# ONOFRE_SWITCH_SHIELD_3_0.net
KiCad netlist of a schematic drawn in EAGLE
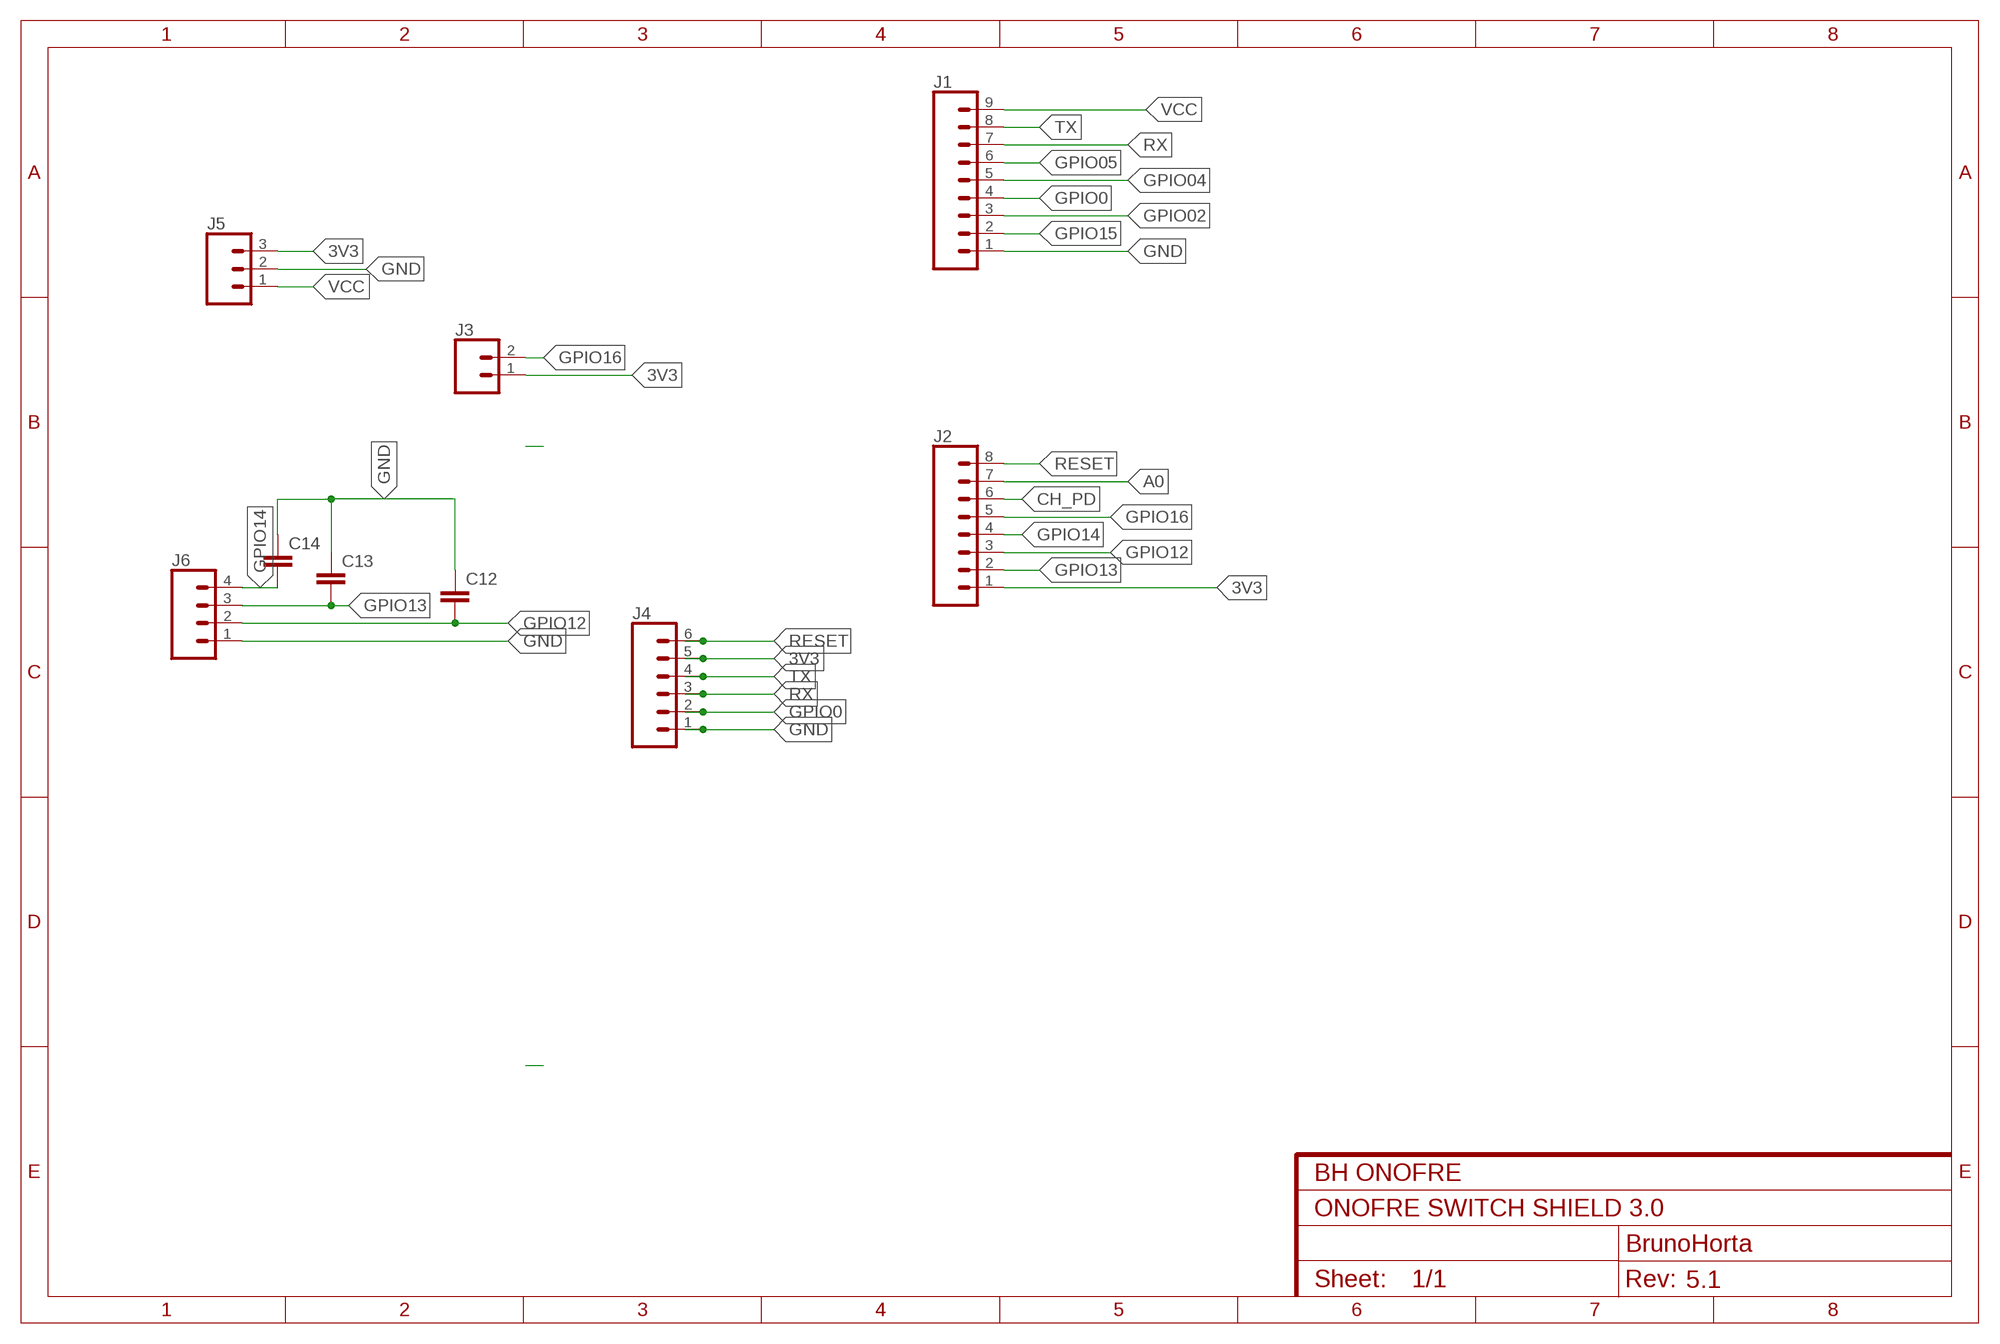
[diagram p0: schematic, sheet 1]

(export (version "E")
  (design (tool "Eeschema 10.0.6"))
  (components
    (comp (ref "C12")
      (value "C-EUC0805")
      (footprint "eagle-import:C0805")
      (libsource (lib "eagle-import") (part "C-EUC0805"))
    )
    (comp (ref "C13")
      (value "C-EUC0805")
      (footprint "eagle-import:C0805")
      (libsource (lib "eagle-import") (part "C-EUC0805"))
    )
    (comp (ref "C14")
      (value "C-EUC0805")
      (footprint "eagle-import:C0805")
      (libsource (lib "eagle-import") (part "C-EUC0805"))
    )
    (comp (ref "J1")
      (value "CONN_09")
      (footprint "eagle-import:1X09")
      (libsource (lib "eagle-import") (part "CONN_09"))
    )
    (comp (ref "J2")
      (value "CONN_08\"")
      (footprint "eagle-import:1X08")
      (libsource (lib "eagle-import") (part "CONN_08{dblquote}"))
    )
    (comp (ref "J3")
      (value "CONN_02")
      (footprint "eagle-import:1X02")
      (libsource (lib "eagle-import") (part "CONN_02"))
    )
    (comp (ref "J4")
      (value "CONN_06NO_SILK_NO_POP")
      (footprint "eagle-import:1X06_NO_SILK")
      (libsource (lib "eagle-import") (part "CONN_06NO_SILK_NO_POP"))
    )
    (comp (ref "J5")
      (value "CONN_03")
      (footprint "eagle-import:1X03")
      (libsource (lib "eagle-import") (part "CONN_03"))
    )
    (comp (ref "J6")
      (value "CONN_04")
      (footprint "eagle-import:1X04")
      (libsource (lib "eagle-import") (part "CONN_04"))
    )
  )
  (nets
    (net (code "1") (name "3V3") (class "Default")
      (node (ref "J2") (pin "1") (pinfunction "1_1") (pintype "passive"))
      (node (ref "J3") (pin "1") (pinfunction "1_1") (pintype "passive"))
      (node (ref "J4") (pin "5") (pinfunction "5_5") (pintype "passive"))
      (node (ref "J5") (pin "3") (pinfunction "3_3") (pintype "passive"))
    )
    (net (code "2") (name "A0") (class "Default")
      (node (ref "J2") (pin "7") (pinfunction "7_7") (pintype "passive"))
    )
    (net (code "3") (name "CH_PD") (class "Default")
      (node (ref "J2") (pin "6") (pinfunction "6_6") (pintype "passive"))
    )
    (net (code "4") (name "GND") (class "Default")
      (node (ref "C12") (pin "1") (pinfunction "1_1") (pintype "passive"))
      (node (ref "C13") (pin "1") (pinfunction "1_1") (pintype "passive"))
      (node (ref "C14") (pin "1") (pinfunction "1_1") (pintype "passive"))
      (node (ref "J1") (pin "1") (pinfunction "1_1") (pintype "passive"))
      (node (ref "J4") (pin "1") (pinfunction "1_1") (pintype "passive"))
      (node (ref "J5") (pin "2") (pinfunction "2_2") (pintype "passive"))
      (node (ref "J6") (pin "1") (pinfunction "1_1") (pintype "passive"))
    )
    (net (code "5") (name "GPIO0") (class "Default")
      (node (ref "J1") (pin "4") (pinfunction "4_4") (pintype "passive"))
      (node (ref "J4") (pin "2") (pinfunction "2_2") (pintype "passive"))
    )
    (net (code "6") (name "GPIO02") (class "Default")
      (node (ref "J1") (pin "3") (pinfunction "3_3") (pintype "passive"))
    )
    (net (code "7") (name "GPIO04") (class "Default")
      (node (ref "J1") (pin "5") (pinfunction "5_5") (pintype "passive"))
    )
    (net (code "8") (name "GPIO05") (class "Default")
      (node (ref "J1") (pin "6") (pinfunction "6_6") (pintype "passive"))
    )
    (net (code "9") (name "GPIO12") (class "Default")
      (node (ref "C12") (pin "2") (pinfunction "2_2") (pintype "passive"))
      (node (ref "J2") (pin "3") (pinfunction "3_3") (pintype "passive"))
      (node (ref "J6") (pin "2") (pinfunction "2_2") (pintype "passive"))
    )
    (net (code "10") (name "GPIO13") (class "Default")
      (node (ref "C13") (pin "2") (pinfunction "2_2") (pintype "passive"))
      (node (ref "J2") (pin "2") (pinfunction "2_2") (pintype "passive"))
      (node (ref "J6") (pin "3") (pinfunction "3_3") (pintype "passive"))
    )
    (net (code "11") (name "GPIO14") (class "Default")
      (node (ref "C14") (pin "2") (pinfunction "2_2") (pintype "passive"))
      (node (ref "J2") (pin "4") (pinfunction "4_4") (pintype "passive"))
      (node (ref "J6") (pin "4") (pinfunction "4_4") (pintype "passive"))
    )
    (net (code "12") (name "GPIO15") (class "Default")
      (node (ref "J1") (pin "2") (pinfunction "2_2") (pintype "passive"))
    )
    (net (code "13") (name "GPIO16") (class "Default")
      (node (ref "J2") (pin "5") (pinfunction "5_5") (pintype "passive"))
      (node (ref "J3") (pin "2") (pinfunction "2_2") (pintype "passive"))
    )
    (net (code "14") (name "RESET") (class "Default")
      (node (ref "J2") (pin "8") (pinfunction "8_8") (pintype "passive"))
      (node (ref "J4") (pin "6") (pinfunction "6_6") (pintype "passive"))
    )
    (net (code "15") (name "RX") (class "Default")
      (node (ref "J1") (pin "7") (pinfunction "7_7") (pintype "passive"))
      (node (ref "J4") (pin "3") (pinfunction "3_3") (pintype "passive"))
    )
    (net (code "16") (name "TX") (class "Default")
      (node (ref "J1") (pin "8") (pinfunction "8_8") (pintype "passive"))
      (node (ref "J4") (pin "4") (pinfunction "4_4") (pintype "passive"))
    )
    (net (code "17") (name "VCC") (class "Default")
      (node (ref "J1") (pin "9") (pinfunction "9_9") (pintype "passive"))
      (node (ref "J5") (pin "1") (pinfunction "1_1") (pintype "passive"))
    )
  )
)
